# Connector.net
KiCad netlist of a schematic drawn in Altium Designer
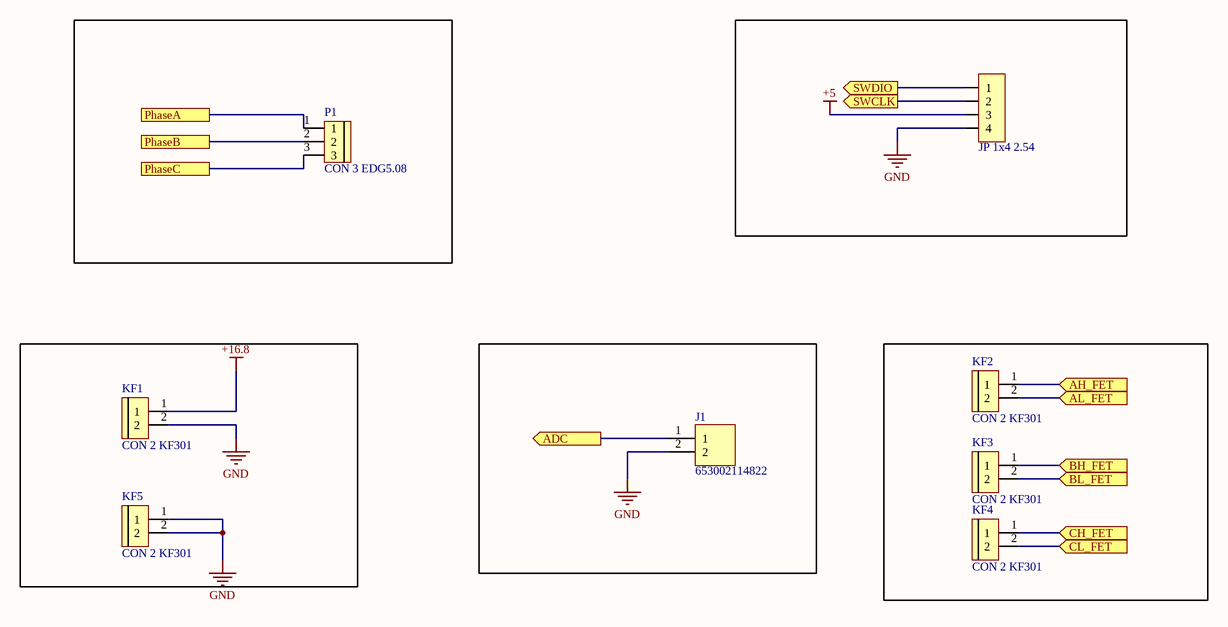
[diagram p0: Connector.SchDoc]

(export (version "E")
  (design (tool "Eeschema 10.0.6"))
  (components
    (comp (ref "J1")
      (value "653002114822")
      (footprint "CON2_50_653002114822_TH_ST")
      (description "2 Pins, 1 Row 1.25mm Pitch, Straight Connector, male")
      (fields (field (name "MANUFACTURER") "JST") (field (name "MATING PART NUMBER") "653002113322"))
      (libsource (lib "Connector") (part "CON-PLG_2X1-50-ST-TH"))
    )
    (comp (ref "JP1")
      (value "JP 1x4 2.54")
      (footprint "JP 1x4 DT")
      (description "Cắm")
      (libsource (lib "Jump") (part "JP 1x4 2.54 Duc Thang"))
    )
    (comp (ref "KF1")
      (value "CON 2 KF301")
      (footprint "Con 2 KF301 5.08")
      (description "Cắm")
      (libsource (lib "Connector") (part "CON 2 KF301"))
    )
    (comp (ref "KF2")
      (value "CON 2 KF301")
      (footprint "Con 2 KF301 5.08")
      (description "Cắm")
      (libsource (lib "Connector") (part "CON 2 KF301"))
    )
    (comp (ref "KF3")
      (value "CON 2 KF301")
      (footprint "Con 2 KF301 5.08")
      (description "Cắm")
      (libsource (lib "Connector") (part "CON 2 KF301"))
    )
    (comp (ref "KF4")
      (value "CON 2 KF301")
      (footprint "Con 2 KF301 5.08")
      (description "Cắm")
      (libsource (lib "Connector") (part "CON 2 KF301"))
    )
    (comp (ref "KF5")
      (value "CON 2 KF301")
      (footprint "Con 2 KF301 5.08")
      (description "Cắm")
      (libsource (lib "Connector") (part "CON 2 KF301"))
    )
    (comp (ref "P1")
      (value "CON 3 EDG5.08")
      (footprint "CON 3 3EDG5.08")
      (description "Cắm")
      (libsource (lib "Connector") (part "CON 3 EDG5.08"))
    )
  )
  (nets
    (net (code "1") (name "+5") (class "Default")
      (node (ref "JP1") (pin "3") (pinfunction "3_3") (pintype "passive"))
    )
    (net (code "2") (name "+16.8") (class "Default")
      (node (ref "KF1") (pin "1") (pinfunction "1_1") (pintype "passive"))
    )
    (net (code "3") (name "/ADC") (class "Default")
      (node (ref "J1") (pin "1") (pinfunction "1_1") (pintype "passive"))
    )
    (net (code "4") (name "/AH_FET") (class "Default")
      (node (ref "KF2") (pin "1") (pinfunction "1_1") (pintype "passive"))
    )
    (net (code "5") (name "/AL_FET") (class "Default")
      (node (ref "KF2") (pin "2") (pinfunction "2_2") (pintype "passive"))
    )
    (net (code "6") (name "/BH_FET") (class "Default")
      (node (ref "KF3") (pin "1") (pinfunction "1_1") (pintype "passive"))
    )
    (net (code "7") (name "/BL_FET") (class "Default")
      (node (ref "KF3") (pin "2") (pinfunction "2_2") (pintype "passive"))
    )
    (net (code "8") (name "/CH_FET") (class "Default")
      (node (ref "KF4") (pin "1") (pinfunction "1_1") (pintype "passive"))
    )
    (net (code "9") (name "/CL_FET") (class "Default")
      (node (ref "KF4") (pin "2") (pinfunction "2_2") (pintype "passive"))
    )
    (net (code "10") (name "/PhaseA") (class "Default")
      (node (ref "P1") (pin "1") (pinfunction "1_1") (pintype "passive"))
    )
    (net (code "11") (name "/PhaseB") (class "Default")
      (node (ref "P1") (pin "2") (pinfunction "2_2") (pintype "passive"))
    )
    (net (code "12") (name "/PhaseC") (class "Default")
      (node (ref "P1") (pin "3") (pinfunction "3_3") (pintype "passive"))
    )
    (net (code "13") (name "/SWCLK") (class "Default")
      (node (ref "JP1") (pin "2") (pinfunction "2_2") (pintype "passive"))
    )
    (net (code "14") (name "/SWDIO") (class "Default")
      (node (ref "JP1") (pin "1") (pinfunction "1_1") (pintype "passive"))
    )
    (net (code "15") (name "GND") (class "Default")
      (node (ref "J1") (pin "2") (pinfunction "2_2") (pintype "passive"))
      (node (ref "JP1") (pin "4") (pinfunction "4_4") (pintype "passive"))
      (node (ref "KF1") (pin "2") (pinfunction "2_2") (pintype "passive"))
      (node (ref "KF5") (pin "1") (pinfunction "1_1") (pintype "passive"))
      (node (ref "KF5") (pin "2") (pinfunction "2_2") (pintype "passive"))
    )
  )
)
